# board.net
KiCad netlist of a schematic drawn in EAGLE
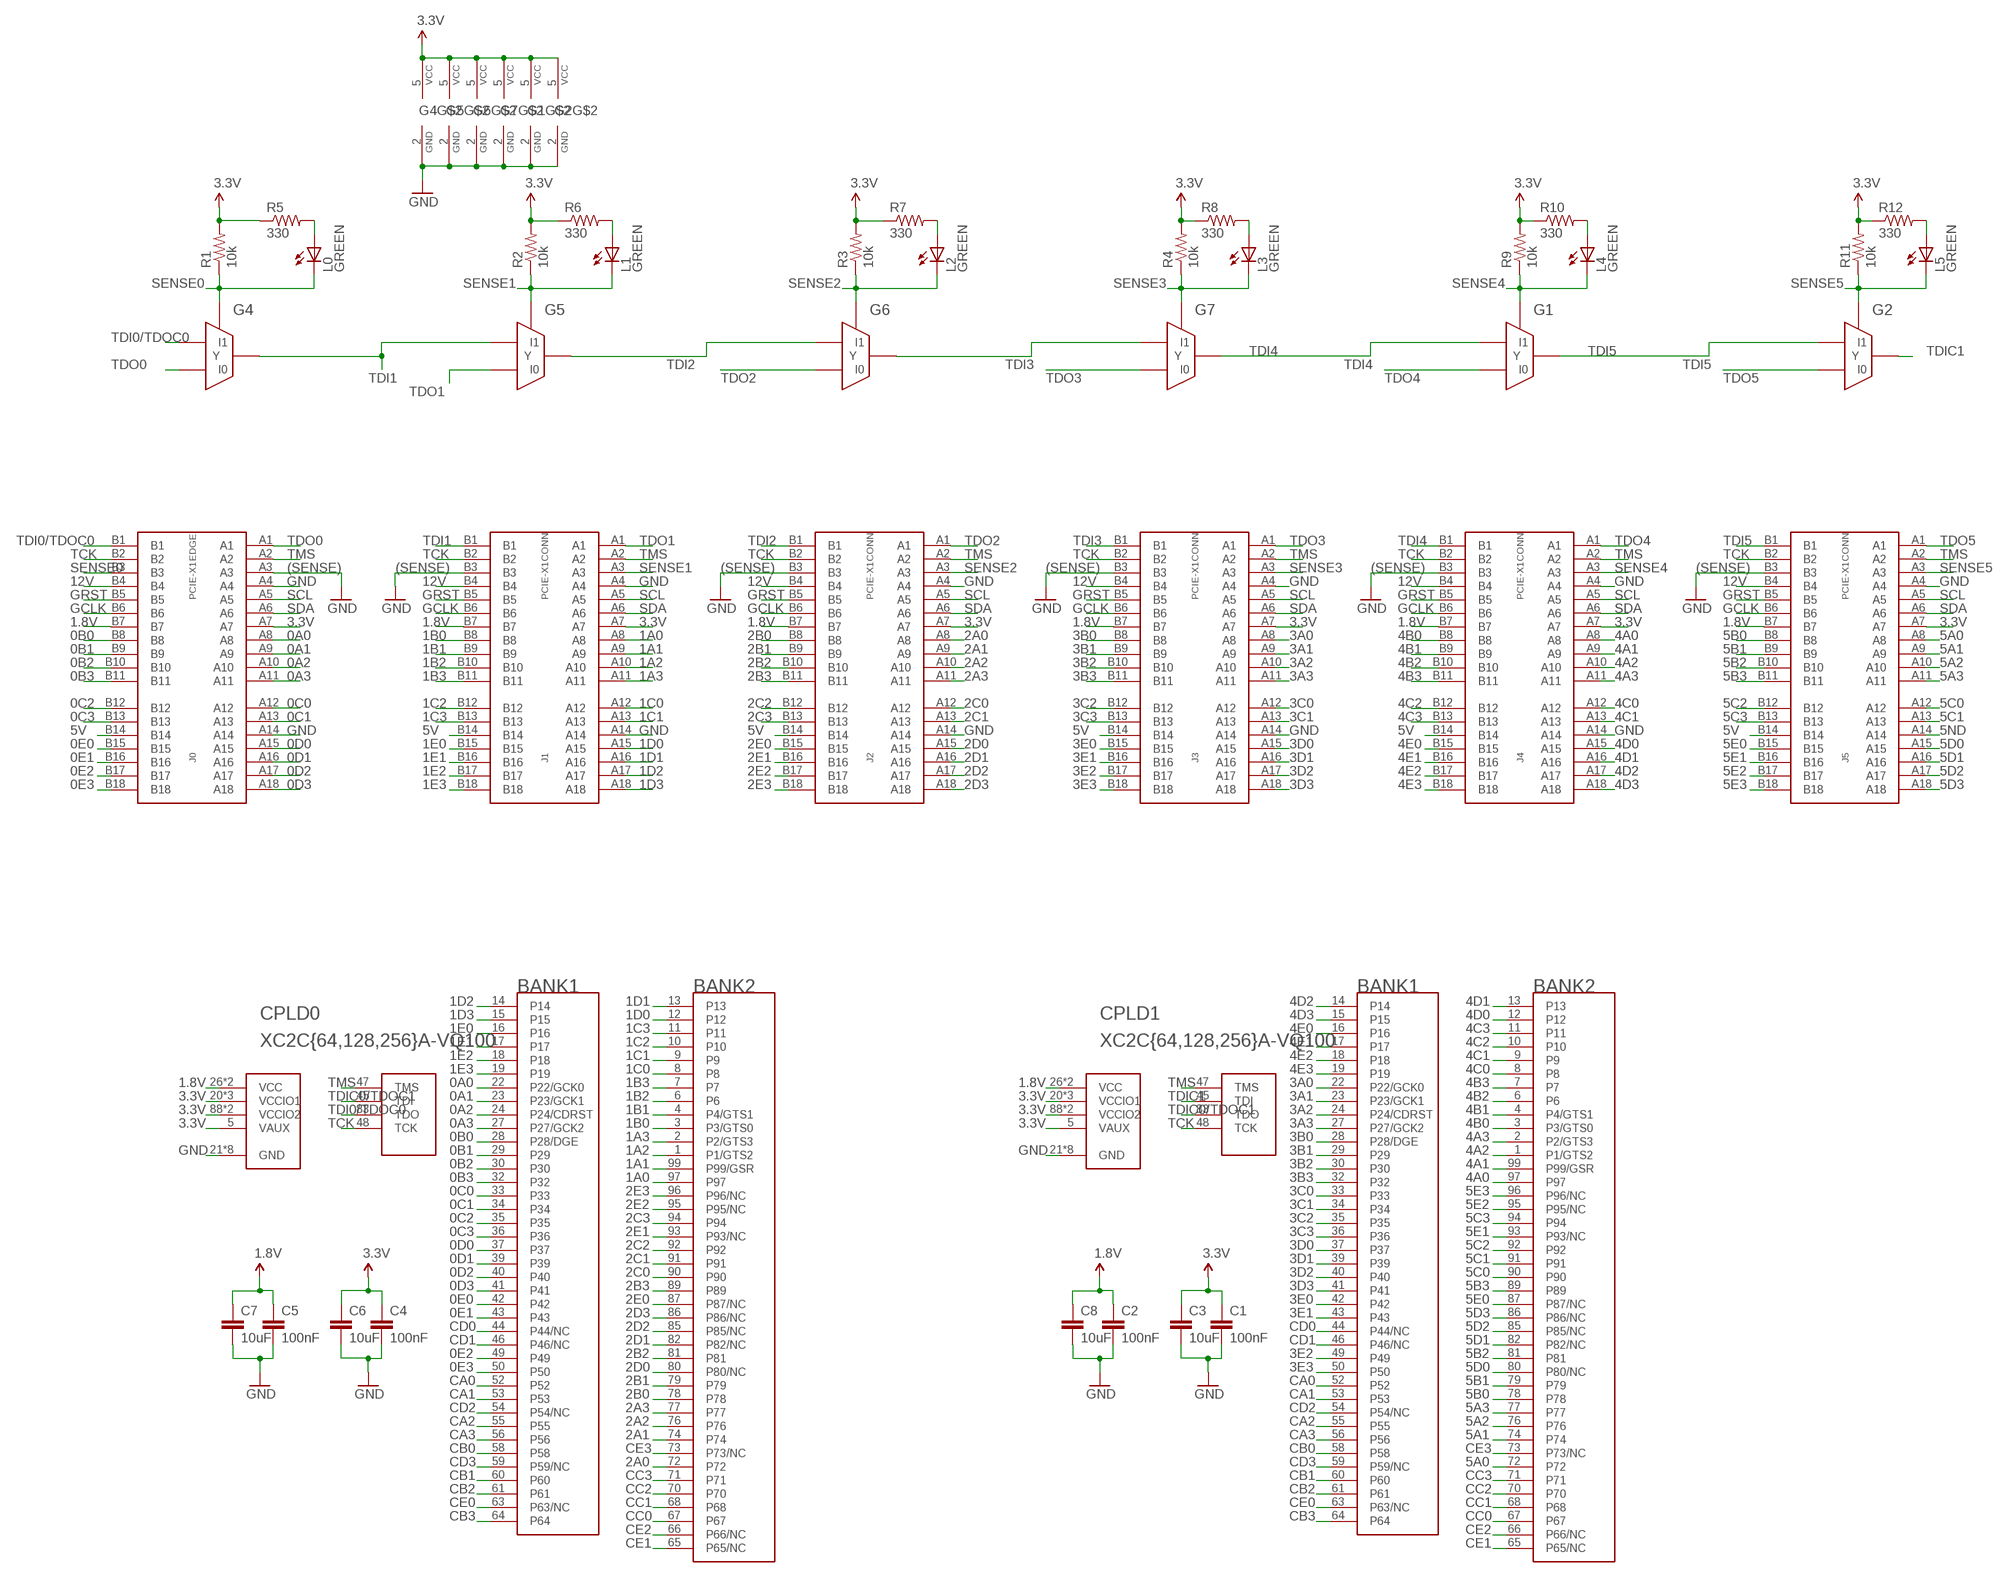
[diagram p0: schematic, sheet 1]

(export (version "E")
  (design (tool "Eeschema 10.0.6"))
  (components
    (comp (ref "C1")
      (value "100nF")
      (footprint "eagle-import:0402-CAP")
      (libsource (lib "eagle-import") (part "CAP0402-CAP"))
    )
    (comp (ref "C2")
      (value "100nF")
      (footprint "eagle-import:0402-CAP")
      (libsource (lib "eagle-import") (part "CAP0402-CAP"))
    )
    (comp (ref "C3")
      (value "10uF")
      (footprint "eagle-import:0805")
      (libsource (lib "eagle-import") (part "CAP0805"))
    )
    (comp (ref "C4")
      (value "100nF")
      (footprint "eagle-import:0402-CAP")
      (libsource (lib "eagle-import") (part "CAP0402-CAP"))
    )
    (comp (ref "C5")
      (value "100nF")
      (footprint "eagle-import:0402-CAP")
      (libsource (lib "eagle-import") (part "CAP0402-CAP"))
    )
    (comp (ref "C6")
      (value "10uF")
      (footprint "eagle-import:0805")
      (libsource (lib "eagle-import") (part "CAP0805"))
    )
    (comp (ref "C7")
      (value "10uF")
      (footprint "eagle-import:0805")
      (libsource (lib "eagle-import") (part "CAP0805"))
    )
    (comp (ref "C8")
      (value "10uF")
      (footprint "eagle-import:0805")
      (libsource (lib "eagle-import") (part "CAP0805"))
    )
    (comp (ref "CPLD0")
      (value "XC2C{64,128,256}A-VQ100")
      (footprint "eagle-import:XILINX_TQ100")
      (libsource (lib "eagle-import") (part "XC2C{64,128,256}A-VQ100"))
    )
    (comp (ref "CPLD1")
      (value "XC2C{64,128,256}A-VQ100")
      (footprint "eagle-import:XILINX_TQ100")
      (libsource (lib "eagle-import") (part "XC2C{64,128,256}A-VQ100"))
    )
    (comp (ref "G1")
      (value "74G157")
      (footprint "eagle-import:SOT363")
      (libsource (lib "eagle-import") (part "74G157"))
    )
    (comp (ref "G2")
      (value "74G157")
      (footprint "eagle-import:SOT363")
      (libsource (lib "eagle-import") (part "74G157"))
    )
    (comp (ref "G4")
      (value "74G157")
      (footprint "eagle-import:SOT363")
      (libsource (lib "eagle-import") (part "74G157"))
    )
    (comp (ref "G5")
      (value "74G157")
      (footprint "eagle-import:SOT363")
      (libsource (lib "eagle-import") (part "74G157"))
    )
    (comp (ref "G6")
      (value "74G157")
      (footprint "eagle-import:SOT363")
      (libsource (lib "eagle-import") (part "74G157"))
    )
    (comp (ref "G7")
      (value "74G157")
      (footprint "eagle-import:SOT363")
      (libsource (lib "eagle-import") (part "74G157"))
    )
    (comp (ref "J0")
      (value "PCIE-X1EDGE")
      (footprint "eagle-import:PCIE-X1-EDGE")
      (libsource (lib "eagle-import") (part "PCIE-X1EDGE"))
    )
    (comp (ref "J1")
      (value "PCIE-X1CONN")
      (footprint "eagle-import:PCIE-X1-CONN")
      (libsource (lib "eagle-import") (part "PCIE-X1CONN"))
    )
    (comp (ref "J2")
      (value "PCIE-X1CONN")
      (footprint "eagle-import:PCIE-X1-CONN")
      (libsource (lib "eagle-import") (part "PCIE-X1CONN"))
    )
    (comp (ref "J3")
      (value "PCIE-X1CONN")
      (footprint "eagle-import:PCIE-X1-CONN")
      (libsource (lib "eagle-import") (part "PCIE-X1CONN"))
    )
    (comp (ref "J4")
      (value "PCIE-X1CONN")
      (footprint "eagle-import:PCIE-X1-CONN")
      (libsource (lib "eagle-import") (part "PCIE-X1CONN"))
    )
    (comp (ref "J5")
      (value "PCIE-X1CONN")
      (footprint "eagle-import:PCIE-X1-CONN")
      (libsource (lib "eagle-import") (part "PCIE-X1CONN"))
    )
    (comp (ref "L0")
      (value "GREEN")
      (footprint "eagle-import:0603_LED")
      (libsource (lib "eagle-import") (part "LED0603"))
    )
    (comp (ref "L1")
      (value "GREEN")
      (footprint "eagle-import:0603_LED")
      (libsource (lib "eagle-import") (part "LED0603"))
    )
    (comp (ref "L2")
      (value "GREEN")
      (footprint "eagle-import:0603_LED")
      (libsource (lib "eagle-import") (part "LED0603"))
    )
    (comp (ref "L3")
      (value "GREEN")
      (footprint "eagle-import:0603_LED")
      (libsource (lib "eagle-import") (part "LED0603"))
    )
    (comp (ref "L4")
      (value "GREEN")
      (footprint "eagle-import:0603_LED")
      (libsource (lib "eagle-import") (part "LED0603"))
    )
    (comp (ref "L5")
      (value "GREEN")
      (footprint "eagle-import:0603_LED")
      (libsource (lib "eagle-import") (part "LED0603"))
    )
    (comp (ref "R1")
      (value "10k")
      (footprint "eagle-import:0603-RES")
      (libsource (lib "eagle-import") (part "RESISTOR0603"))
    )
    (comp (ref "R2")
      (value "10k")
      (footprint "eagle-import:0603-RES")
      (libsource (lib "eagle-import") (part "RESISTOR0603"))
    )
    (comp (ref "R3")
      (value "10k")
      (footprint "eagle-import:0603-RES")
      (libsource (lib "eagle-import") (part "RESISTOR0603"))
    )
    (comp (ref "R4")
      (value "10k")
      (footprint "eagle-import:0603-RES")
      (libsource (lib "eagle-import") (part "RESISTOR0603"))
    )
    (comp (ref "R5")
      (value "330")
      (footprint "eagle-import:0603-RES")
      (libsource (lib "eagle-import") (part "RESISTOR0603"))
    )
    (comp (ref "R6")
      (value "330")
      (footprint "eagle-import:0603-RES")
      (libsource (lib "eagle-import") (part "RESISTOR0603"))
    )
    (comp (ref "R7")
      (value "330")
      (footprint "eagle-import:0603-RES")
      (libsource (lib "eagle-import") (part "RESISTOR0603"))
    )
    (comp (ref "R8")
      (value "330")
      (footprint "eagle-import:0603-RES")
      (libsource (lib "eagle-import") (part "RESISTOR0603"))
    )
    (comp (ref "R9")
      (value "10k")
      (footprint "eagle-import:0603-RES")
      (libsource (lib "eagle-import") (part "RESISTOR0603"))
    )
    (comp (ref "R10")
      (value "330")
      (footprint "eagle-import:0603-RES")
      (libsource (lib "eagle-import") (part "RESISTOR0603"))
    )
    (comp (ref "R11")
      (value "10k")
      (footprint "eagle-import:0603-RES")
      (libsource (lib "eagle-import") (part "RESISTOR0603"))
    )
    (comp (ref "R12")
      (value "330")
      (footprint "eagle-import:0603-RES")
      (libsource (lib "eagle-import") (part "RESISTOR0603"))
    )
  )
  (nets
    (net (code "1") (name "/0A0") (class "Default")
      (node (ref "CPLD0") (pin "22") (pinfunction "P22/GCK0_22") (pintype "bidirectional"))
      (node (ref "J0") (pin "A8") (pinfunction "A8_A8") (pintype "bidirectional"))
    )
    (net (code "2") (name "/0A1") (class "Default")
      (node (ref "CPLD0") (pin "23") (pinfunction "P23/GCK1_23") (pintype "bidirectional"))
      (node (ref "J0") (pin "A9") (pinfunction "A9_A9") (pintype "bidirectional"))
    )
    (net (code "3") (name "/0A2") (class "Default")
      (node (ref "CPLD0") (pin "24") (pinfunction "P24/CDRST_24") (pintype "bidirectional"))
      (node (ref "J0") (pin "A10") (pinfunction "A10_A10") (pintype "bidirectional"))
    )
    (net (code "4") (name "/0A3") (class "Default")
      (node (ref "CPLD0") (pin "27") (pinfunction "P27/GCK2_27") (pintype "bidirectional"))
      (node (ref "J0") (pin "A11") (pinfunction "A11_A11") (pintype "bidirectional"))
    )
    (net (code "5") (name "/0B0") (class "Default")
      (node (ref "CPLD0") (pin "28") (pinfunction "P28/DGE_28") (pintype "bidirectional"))
      (node (ref "J0") (pin "B8") (pinfunction "B8_B8") (pintype "bidirectional"))
    )
    (net (code "6") (name "/0B1") (class "Default")
      (node (ref "CPLD0") (pin "29") (pinfunction "P29_29") (pintype "bidirectional"))
      (node (ref "J0") (pin "B9") (pinfunction "B9_B9") (pintype "bidirectional"))
    )
    (net (code "7") (name "/0B2") (class "Default")
      (node (ref "CPLD0") (pin "30") (pinfunction "P30_30") (pintype "bidirectional"))
      (node (ref "J0") (pin "B10") (pinfunction "B10_B10") (pintype "bidirectional"))
    )
    (net (code "8") (name "/0B3") (class "Default")
      (node (ref "CPLD0") (pin "32") (pinfunction "P32_32") (pintype "bidirectional"))
      (node (ref "J0") (pin "B11") (pinfunction "B11_B11") (pintype "bidirectional"))
    )
    (net (code "9") (name "/0C0") (class "Default")
      (node (ref "CPLD0") (pin "33") (pinfunction "P33_33") (pintype "bidirectional"))
      (node (ref "J0") (pin "A12") (pinfunction "A12_A12") (pintype "bidirectional"))
    )
    (net (code "10") (name "/0C1") (class "Default")
      (node (ref "CPLD0") (pin "34") (pinfunction "P34_34") (pintype "bidirectional"))
      (node (ref "J0") (pin "A13") (pinfunction "A13_A13") (pintype "bidirectional"))
    )
    (net (code "11") (name "/0C2") (class "Default")
      (node (ref "CPLD0") (pin "35") (pinfunction "P35_35") (pintype "bidirectional"))
      (node (ref "J0") (pin "B12") (pinfunction "B12_B12") (pintype "bidirectional"))
    )
    (net (code "12") (name "/0C3") (class "Default")
      (node (ref "CPLD0") (pin "36") (pinfunction "P36_36") (pintype "bidirectional"))
      (node (ref "J0") (pin "B13") (pinfunction "B13_B13") (pintype "bidirectional"))
    )
    (net (code "13") (name "/0D0") (class "Default")
      (node (ref "CPLD0") (pin "37") (pinfunction "P37_37") (pintype "bidirectional"))
      (node (ref "J0") (pin "A15") (pinfunction "A15_A15") (pintype "bidirectional"))
    )
    (net (code "14") (name "/0D1") (class "Default")
      (node (ref "CPLD0") (pin "39") (pinfunction "P39_39") (pintype "bidirectional"))
      (node (ref "J0") (pin "A16") (pinfunction "A16_A16") (pintype "bidirectional"))
    )
    (net (code "15") (name "/0D2") (class "Default")
      (node (ref "CPLD0") (pin "40") (pinfunction "P40_40") (pintype "bidirectional"))
      (node (ref "J0") (pin "A17") (pinfunction "A17_A17") (pintype "bidirectional"))
    )
    (net (code "16") (name "/0D3") (class "Default")
      (node (ref "CPLD0") (pin "41") (pinfunction "P41_41") (pintype "bidirectional"))
      (node (ref "J0") (pin "A18") (pinfunction "A18_A18") (pintype "bidirectional"))
    )
    (net (code "17") (name "/0E0") (class "Default")
      (node (ref "CPLD0") (pin "42") (pinfunction "P42_42") (pintype "bidirectional"))
      (node (ref "J0") (pin "B15") (pinfunction "B15_B15") (pintype "bidirectional"))
    )
    (net (code "18") (name "/0E1") (class "Default")
      (node (ref "CPLD0") (pin "43") (pinfunction "P43_43") (pintype "bidirectional"))
      (node (ref "J0") (pin "B16") (pinfunction "B16_B16") (pintype "bidirectional"))
    )
    (net (code "19") (name "/0E2") (class "Default")
      (node (ref "CPLD0") (pin "49") (pinfunction "P49_49") (pintype "bidirectional"))
      (node (ref "J0") (pin "B17") (pinfunction "B17_B17") (pintype "bidirectional"))
    )
    (net (code "20") (name "/0E3") (class "Default")
      (node (ref "CPLD0") (pin "50") (pinfunction "P50_50") (pintype "bidirectional"))
      (node (ref "J0") (pin "B18") (pinfunction "B18_B18") (pintype "bidirectional"))
    )
    (net (code "21") (name "/1A0") (class "Default")
      (node (ref "CPLD0") (pin "97") (pinfunction "P97_97") (pintype "bidirectional"))
      (node (ref "J1") (pin "A8") (pinfunction "A8_A8") (pintype "bidirectional"))
    )
    (net (code "22") (name "/1A1") (class "Default")
      (node (ref "CPLD0") (pin "99") (pinfunction "P99/GSR_99") (pintype "bidirectional"))
      (node (ref "J1") (pin "A9") (pinfunction "A9_A9") (pintype "bidirectional"))
    )
    (net (code "23") (name "/1A2") (class "Default")
      (node (ref "CPLD0") (pin "1") (pinfunction "P1/GTS2_1") (pintype "bidirectional"))
      (node (ref "J1") (pin "A10") (pinfunction "A10_A10") (pintype "bidirectional"))
    )
    (net (code "24") (name "/1A3") (class "Default")
      (node (ref "CPLD0") (pin "2") (pinfunction "P2/GTS3_2") (pintype "bidirectional"))
      (node (ref "J1") (pin "A11") (pinfunction "A11_A11") (pintype "bidirectional"))
    )
    (net (code "25") (name "/1B0") (class "Default")
      (node (ref "CPLD0") (pin "3") (pinfunction "P3/GTS0_3") (pintype "bidirectional"))
      (node (ref "J1") (pin "B8") (pinfunction "B8_B8") (pintype "bidirectional"))
    )
    (net (code "26") (name "/1B1") (class "Default")
      (node (ref "CPLD0") (pin "4") (pinfunction "P4/GTS1_4") (pintype "bidirectional"))
      (node (ref "J1") (pin "B9") (pinfunction "B9_B9") (pintype "bidirectional"))
    )
    (net (code "27") (name "/1B2") (class "Default")
      (node (ref "CPLD0") (pin "6") (pinfunction "P6_6") (pintype "bidirectional"))
      (node (ref "J1") (pin "B10") (pinfunction "B10_B10") (pintype "bidirectional"))
    )
    (net (code "28") (name "/1B3") (class "Default")
      (node (ref "CPLD0") (pin "7") (pinfunction "P7_7") (pintype "bidirectional"))
      (node (ref "J1") (pin "B11") (pinfunction "B11_B11") (pintype "bidirectional"))
    )
    (net (code "29") (name "/1C0") (class "Default")
      (node (ref "CPLD0") (pin "8") (pinfunction "P8_8") (pintype "bidirectional"))
      (node (ref "J1") (pin "A12") (pinfunction "A12_A12") (pintype "bidirectional"))
    )
    (net (code "30") (name "/1C1") (class "Default")
      (node (ref "CPLD0") (pin "9") (pinfunction "P9_9") (pintype "bidirectional"))
      (node (ref "J1") (pin "A13") (pinfunction "A13_A13") (pintype "bidirectional"))
    )
    (net (code "31") (name "/1C2") (class "Default")
      (node (ref "CPLD0") (pin "10") (pinfunction "P10_10") (pintype "bidirectional"))
      (node (ref "J1") (pin "B12") (pinfunction "B12_B12") (pintype "bidirectional"))
    )
    (net (code "32") (name "/1C3") (class "Default")
      (node (ref "CPLD0") (pin "11") (pinfunction "P11_11") (pintype "bidirectional"))
      (node (ref "J1") (pin "B13") (pinfunction "B13_B13") (pintype "bidirectional"))
    )
    (net (code "33") (name "/1D0") (class "Default")
      (node (ref "CPLD0") (pin "12") (pinfunction "P12_12") (pintype "bidirectional"))
      (node (ref "J1") (pin "A15") (pinfunction "A15_A15") (pintype "bidirectional"))
    )
    (net (code "34") (name "/1D1") (class "Default")
      (node (ref "CPLD0") (pin "13") (pinfunction "P13_13") (pintype "bidirectional"))
      (node (ref "J1") (pin "A16") (pinfunction "A16_A16") (pintype "bidirectional"))
    )
    (net (code "35") (name "/1D2") (class "Default")
      (node (ref "CPLD0") (pin "14") (pinfunction "P14_14") (pintype "bidirectional"))
      (node (ref "J1") (pin "A17") (pinfunction "A17_A17") (pintype "bidirectional"))
    )
    (net (code "36") (name "/1D3") (class "Default")
      (node (ref "CPLD0") (pin "15") (pinfunction "P15_15") (pintype "bidirectional"))
      (node (ref "J1") (pin "A18") (pinfunction "A18_A18") (pintype "bidirectional"))
    )
    (net (code "37") (name "/1E0") (class "Default")
      (node (ref "CPLD0") (pin "16") (pinfunction "P16_16") (pintype "bidirectional"))
      (node (ref "J1") (pin "B15") (pinfunction "B15_B15") (pintype "bidirectional"))
    )
    (net (code "38") (name "/1E1") (class "Default")
      (node (ref "CPLD0") (pin "17") (pinfunction "P17_17") (pintype "bidirectional"))
      (node (ref "J1") (pin "B16") (pinfunction "B16_B16") (pintype "bidirectional"))
    )
    (net (code "39") (name "/1E2") (class "Default")
      (node (ref "CPLD0") (pin "18") (pinfunction "P18_18") (pintype "bidirectional"))
      (node (ref "J1") (pin "B17") (pinfunction "B17_B17") (pintype "bidirectional"))
    )
    (net (code "40") (name "/1E3") (class "Default")
      (node (ref "CPLD0") (pin "19") (pinfunction "P19_19") (pintype "bidirectional"))
      (node (ref "J1") (pin "B18") (pinfunction "B18_B18") (pintype "bidirectional"))
    )
    (net (code "41") (name "/2A0") (class "Default")
      (node (ref "CPLD0") (pin "72") (pinfunction "P72_72") (pintype "bidirectional"))
      (node (ref "J2") (pin "A8") (pinfunction "A8_A8") (pintype "bidirectional"))
    )
    (net (code "42") (name "/2A1") (class "Default")
      (node (ref "CPLD0") (pin "74") (pinfunction "P74_74") (pintype "bidirectional"))
      (node (ref "J2") (pin "A9") (pinfunction "A9_A9") (pintype "bidirectional"))
    )
    (net (code "43") (name "/2A2") (class "Default")
      (node (ref "CPLD0") (pin "76") (pinfunction "P76_76") (pintype "bidirectional"))
      (node (ref "J2") (pin "A10") (pinfunction "A10_A10") (pintype "bidirectional"))
    )
    (net (code "44") (name "/2A3") (class "Default")
      (node (ref "CPLD0") (pin "77") (pinfunction "P77_77") (pintype "bidirectional"))
      (node (ref "J2") (pin "A11") (pinfunction "A11_A11") (pintype "bidirectional"))
    )
    (net (code "45") (name "/2B0") (class "Default")
      (node (ref "CPLD0") (pin "78") (pinfunction "P78_78") (pintype "bidirectional"))
      (node (ref "J2") (pin "B8") (pinfunction "B8_B8") (pintype "bidirectional"))
    )
    (net (code "46") (name "/2B1") (class "Default")
      (node (ref "CPLD0") (pin "79") (pinfunction "P79_79") (pintype "bidirectional"))
      (node (ref "J2") (pin "B9") (pinfunction "B9_B9") (pintype "bidirectional"))
    )
    (net (code "47") (name "/2B2") (class "Default")
      (node (ref "CPLD0") (pin "81") (pinfunction "P81_81") (pintype "bidirectional"))
      (node (ref "J2") (pin "B10") (pinfunction "B10_B10") (pintype "bidirectional"))
    )
    (net (code "48") (name "/2B3") (class "Default")
      (node (ref "CPLD0") (pin "89") (pinfunction "P89_89") (pintype "bidirectional"))
      (node (ref "J2") (pin "B11") (pinfunction "B11_B11") (pintype "bidirectional"))
    )
    (net (code "49") (name "/2C0") (class "Default")
      (node (ref "CPLD0") (pin "90") (pinfunction "P90_90") (pintype "bidirectional"))
      (node (ref "J2") (pin "A12") (pinfunction "A12_A12") (pintype "bidirectional"))
    )
    (net (code "50") (name "/2C1") (class "Default")
      (node (ref "CPLD0") (pin "91") (pinfunction "P91_91") (pintype "bidirectional"))
      (node (ref "J2") (pin "A13") (pinfunction "A13_A13") (pintype "bidirectional"))
    )
    (net (code "51") (name "/2C2") (class "Default")
      (node (ref "CPLD0") (pin "92") (pinfunction "P92_92") (pintype "bidirectional"))
      (node (ref "J2") (pin "B12") (pinfunction "B12_B12") (pintype "bidirectional"))
    )
    (net (code "52") (name "/2C3") (class "Default")
      (node (ref "CPLD0") (pin "94") (pinfunction "P94_94") (pintype "bidirectional"))
      (node (ref "J2") (pin "B13") (pinfunction "B13_B13") (pintype "bidirectional"))
    )
    (net (code "53") (name "/2D0") (class "Default")
      (node (ref "CPLD0") (pin "80") (pinfunction "P80/NC_80") (pintype "bidirectional"))
      (node (ref "J2") (pin "A15") (pinfunction "A15_A15") (pintype "bidirectional"))
    )
    (net (code "54") (name "/2D1") (class "Default")
      (node (ref "CPLD0") (pin "82") (pinfunction "P82/NC_82") (pintype "bidirectional"))
      (node (ref "J2") (pin "A16") (pinfunction "A16_A16") (pintype "bidirectional"))
    )
    (net (code "55") (name "/2D2") (class "Default")
      (node (ref "CPLD0") (pin "85") (pinfunction "P85/NC_85") (pintype "bidirectional"))
      (node (ref "J2") (pin "A17") (pinfunction "A17_A17") (pintype "bidirectional"))
    )
    (net (code "56") (name "/2D3") (class "Default")
      (node (ref "CPLD0") (pin "86") (pinfunction "P86/NC_86") (pintype "bidirectional"))
      (node (ref "J2") (pin "A18") (pinfunction "A18_A18") (pintype "bidirectional"))
    )
    (net (code "57") (name "/2E0") (class "Default")
      (node (ref "CPLD0") (pin "87") (pinfunction "P87/NC_87") (pintype "bidirectional"))
      (node (ref "J2") (pin "B15") (pinfunction "B15_B15") (pintype "bidirectional"))
    )
    (net (code "58") (name "/2E1") (class "Default")
      (node (ref "CPLD0") (pin "93") (pinfunction "P93/NC_93") (pintype "bidirectional"))
      (node (ref "J2") (pin "B16") (pinfunction "B16_B16") (pintype "bidirectional"))
    )
    (net (code "59") (name "/2E2") (class "Default")
      (node (ref "CPLD0") (pin "95") (pinfunction "P95/NC_95") (pintype "bidirectional"))
      (node (ref "J2") (pin "B17") (pinfunction "B17_B17") (pintype "bidirectional"))
    )
    (net (code "60") (name "/2E3") (class "Default")
      (node (ref "CPLD0") (pin "96") (pinfunction "P96/NC_96") (pintype "bidirectional"))
      (node (ref "J2") (pin "B18") (pinfunction "B18_B18") (pintype "bidirectional"))
    )
    (net (code "61") (name "/3A0") (class "Default")
      (node (ref "CPLD1") (pin "22") (pinfunction "P22/GCK0_22") (pintype "bidirectional"))
      (node (ref "J3") (pin "A8") (pinfunction "A8_A8") (pintype "bidirectional"))
    )
    (net (code "62") (name "/3A1") (class "Default")
      (node (ref "CPLD1") (pin "23") (pinfunction "P23/GCK1_23") (pintype "bidirectional"))
      (node (ref "J3") (pin "A9") (pinfunction "A9_A9") (pintype "bidirectional"))
    )
    (net (code "63") (name "/3A2") (class "Default")
      (node (ref "CPLD1") (pin "24") (pinfunction "P24/CDRST_24") (pintype "bidirectional"))
      (node (ref "J3") (pin "A10") (pinfunction "A10_A10") (pintype "bidirectional"))
    )
    (net (code "64") (name "/3A3") (class "Default")
      (node (ref "CPLD1") (pin "27") (pinfunction "P27/GCK2_27") (pintype "bidirectional"))
      (node (ref "J3") (pin "A11") (pinfunction "A11_A11") (pintype "bidirectional"))
    )
    (net (code "65") (name "/3B0") (class "Default")
      (node (ref "CPLD1") (pin "28") (pinfunction "P28/DGE_28") (pintype "bidirectional"))
      (node (ref "J3") (pin "B8") (pinfunction "B8_B8") (pintype "bidirectional"))
    )
    (net (code "66") (name "/3B1") (class "Default")
      (node (ref "CPLD1") (pin "29") (pinfunction "P29_29") (pintype "bidirectional"))
      (node (ref "J3") (pin "B9") (pinfunction "B9_B9") (pintype "bidirectional"))
    )
    (net (code "67") (name "/3B2") (class "Default")
      (node (ref "CPLD1") (pin "30") (pinfunction "P30_30") (pintype "bidirectional"))
      (node (ref "J3") (pin "B10") (pinfunction "B10_B10") (pintype "bidirectional"))
    )
    (net (code "68") (name "/3B3") (class "Default")
      (node (ref "CPLD1") (pin "32") (pinfunction "P32_32") (pintype "bidirectional"))
      (node (ref "J3") (pin "B11") (pinfunction "B11_B11") (pintype "bidirectional"))
    )
    (net (code "69") (name "/3C0") (class "Default")
      (node (ref "CPLD1") (pin "33") (pinfunction "P33_33") (pintype "bidirectional"))
      (node (ref "J3") (pin "A12") (pinfunction "A12_A12") (pintype "bidirectional"))
    )
    (net (code "70") (name "/3C1") (class "Default")
      (node (ref "CPLD1") (pin "34") (pinfunction "P34_34") (pintype "bidirectional"))
      (node (ref "J3") (pin "A13") (pinfunction "A13_A13") (pintype "bidirectional"))
    )
    (net (code "71") (name "/3C2") (class "Default")
      (node (ref "CPLD1") (pin "35") (pinfunction "P35_35") (pintype "bidirectional"))
      (node (ref "J3") (pin "B12") (pinfunction "B12_B12") (pintype "bidirectional"))
    )
    (net (code "72") (name "/3C3") (class "Default")
      (node (ref "CPLD1") (pin "36") (pinfunction "P36_36") (pintype "bidirectional"))
      (node (ref "J3") (pin "B13") (pinfunction "B13_B13") (pintype "bidirectional"))
    )
    (net (code "73") (name "/3D0") (class "Default")
      (node (ref "CPLD1") (pin "37") (pinfunction "P37_37") (pintype "bidirectional"))
      (node (ref "J3") (pin "A15") (pinfunction "A15_A15") (pintype "bidirectional"))
    )
    (net (code "74") (name "/3D1") (class "Default")
      (node (ref "CPLD1") (pin "39") (pinfunction "P39_39") (pintype "bidirectional"))
      (node (ref "J3") (pin "A16") (pinfunction "A16_A16") (pintype "bidirectional"))
    )
    (net (code "75") (name "/3D2") (class "Default")
      (node (ref "CPLD1") (pin "40") (pinfunction "P40_40") (pintype "bidirectional"))
      (node (ref "J3") (pin "A17") (pinfunction "A17_A17") (pintype "bidirectional"))
    )
    (net (code "76") (name "/3D3") (class "Default")
      (node (ref "CPLD1") (pin "41") (pinfunction "P41_41") (pintype "bidirectional"))
      (node (ref "J3") (pin "A18") (pinfunction "A18_A18") (pintype "bidirectional"))
    )
    (net (code "77") (name "/3E0") (class "Default")
      (node (ref "CPLD1") (pin "42") (pinfunction "P42_42") (pintype "bidirectional"))
      (node (ref "J3") (pin "B15") (pinfunction "B15_B15") (pintype "bidirectional"))
    )
    (net (code "78") (name "/3E1") (class "Default")
      (node (ref "CPLD1") (pin "43") (pinfunction "P43_43") (pintype "bidirectional"))
      (node (ref "J3") (pin "B16") (pinfunction "B16_B16") (pintype "bidirectional"))
    )
    (net (code "79") (name "/3E2") (class "Default")
      (node (ref "CPLD1") (pin "49") (pinfunction "P49_49") (pintype "bidirectional"))
      (node (ref "J3") (pin "B17") (pinfunction "B17_B17") (pintype "bidirectional"))
    )
    (net (code "80") (name "/3E3") (class "Default")
      (node (ref "CPLD1") (pin "50") (pinfunction "P50_50") (pintype "bidirectional"))
      (node (ref "J3") (pin "B18") (pinfunction "B18_B18") (pintype "bidirectional"))
    )
    (net (code "81") (name "/4A0") (class "Default")
      (node (ref "CPLD1") (pin "97") (pinfunction "P97_97") (pintype "bidirectional"))
      (node (ref "J4") (pin "A8") (pinfunction "A8_A8") (pintype "bidirectional"))
    )
    (net (code "82") (name "/4A1") (class "Default")
      (node (ref "CPLD1") (pin "99") (pinfunction "P99/GSR_99") (pintype "bidirectional"))
      (node (ref "J4") (pin "A9") (pinfunction "A9_A9") (pintype "bidirectional"))
    )
    (net (code "83") (name "/4A2") (class "Default")
      (node (ref "CPLD1") (pin "1") (pinfunction "P1/GTS2_1") (pintype "bidirectional"))
      (node (ref "J4") (pin "A10") (pinfunction "A10_A10") (pintype "bidirectional"))
    )
    (net (code "84") (name "/4A3") (class "Default")
      (node (ref "CPLD1") (pin "2") (pinfunction "P2/GTS3_2") (pintype "bidirectional"))
      (node (ref "J4") (pin "A11") (pinfunction "A11_A11") (pintype "bidirectional"))
    )
    (net (code "85") (name "/4B0") (class "Default")
      (node (ref "CPLD1") (pin "3") (pinfunction "P3/GTS0_3") (pintype "bidirectional"))
      (node (ref "J4") (pin "B8") (pinfunction "B8_B8") (pintype "bidirectional"))
    )
    (net (code "86") (name "/4B1") (class "Default")
      (node (ref "CPLD1") (pin "4") (pinfunction "P4/GTS1_4") (pintype "bidirectional"))
      (node (ref "J4") (pin "B9") (pinfunction "B9_B9") (pintype "bidirectional"))
    )
    (net (code "87") (name "/4B2") (class "Default")
      (node (ref "CPLD1") (pin "6") (pinfunction "P6_6") (pintype "bidirectional"))
      (node (ref "J4") (pin "B10") (pinfunction "B10_B10") (pintype "bidirectional"))
    )
    (net (code "88") (name "/4B3") (class "Default")
      (node (ref "CPLD1") (pin "7") (pinfunction "P7_7") (pintype "bidirectional"))
      (node (ref "J4") (pin "B11") (pinfunction "B11_B11") (pintype "bidirectional"))
    )
    (net (code "89") (name "/4C0") (class "Default")
      (node (ref "CPLD1") (pin "8") (pinfunction "P8_8") (pintype "bidirectional"))
      (node (ref "J4") (pin "A12") (pinfunction "A12_A12") (pintype "bidirectional"))
    )
    (net (code "90") (name "/4C1") (class "Default")
      (node (ref "CPLD1") (pin "9") (pinfunction "P9_9") (pintype "bidirectional"))
      (node (ref "J4") (pin "A13") (pinfunction "A13_A13") (pintype "bidirectional"))
    )
    (net (code "91") (name "/4C2") (class "Default")
      (node (ref "CPLD1") (pin "10") (pinfunction "P10_10") (pintype "bidirectional"))
      (node (ref "J4") (pin "B12") (pinfunction "B12_B12") (pintype "bidirectional"))
    )
    (net (code "92") (name "/4C3") (class "Default")
      (node (ref "CPLD1") (pin "11") (pinfunction "P11_11") (pintype "bidirectional"))
      (node (ref "J4") (pin "B13") (pinfunction "B13_B13") (pintype "bidirectional"))
    )
    (net (code "93") (name "/4D0") (class "Default")
      (node (ref "CPLD1") (pin "12") (pinfunction "P12_12") (pintype "bidirectional"))
      (node (ref "J4") (pin "A15") (pinfunction "A15_A15") (pintype "bidirectional"))
    )
    (net (code "94") (name "/4D1") (class "Default")
      (node (ref "CPLD1") (pin "13") (pinfunction "P13_13") (pintype "bidirectional"))
      (node (ref "J4") (pin "A16") (pinfunction "A16_A16") (pintype "bidirectional"))
    )
    (net (code "95") (name "/4D2") (class "Default")
      (node (ref "CPLD1") (pin "14") (pinfunction "P14_14") (pintype "bidirectional"))
      (node (ref "J4") (pin "A17") (pinfunction "A17_A17") (pintype "bidirectional"))
    )
    (net (code "96") (name "/4D3") (class "Default")
      (node (ref "CPLD1") (pin "15") (pinfunction "P15_15") (pintype "bidirectional"))
      (node (ref "J4") (pin "A18") (pinfunction "A18_A18") (pintype "bidirectional"))
    )
    (net (code "97") (name "/4E0") (class "Default")
      (node (ref "CPLD1") (pin "16") (pinfunction "P16_16") (pintype "bidirectional"))
      (node (ref "J4") (pin "B15") (pinfunction "B15_B15") (pintype "bidirectional"))
    )
    (net (code "98") (name "/4E1") (class "Default")
      (node (ref "CPLD1") (pin "17") (pinfunction "P17_17") (pintype "bidirectional"))
      (node (ref "J4") (pin "B16") (pinfunction "B16_B16") (pintype "bidirectional"))
    )
    (net (code "99") (name "/4E2") (class "Default")
      (node (ref "CPLD1") (pin "18") (pinfunction "P18_18") (pintype "bidirectional"))
      (node (ref "J4") (pin "B17") (pinfunction "B17_B17") (pintype "bidirectional"))
    )
    (net (code "100") (name "/4E3") (class "Default")
      (node (ref "CPLD1") (pin "19") (pinfunction "P19_19") (pintype "bidirectional"))
      (node (ref "J4") (pin "B18") (pinfunction "B18_B18") (pintype "bidirectional"))
    )
    (net (code "101") (name "/5A0") (class "Default")
      (node (ref "CPLD1") (pin "72") (pinfunction "P72_72") (pintype "bidirectional"))
      (node (ref "J5") (pin "A8") (pinfunction "A8_A8") (pintype "bidirectional"))
    )
    (net (code "102") (name "/5A1") (class "Default")
      (node (ref "CPLD1") (pin "74") (pinfunction "P74_74") (pintype "bidirectional"))
      (node (ref "J5") (pin "A9") (pinfunction "A9_A9") (pintype "bidirectional"))
    )
    (net (code "103") (name "/5A2") (class "Default")
      (node (ref "CPLD1") (pin "76") (pinfunction "P76_76") (pintype "bidirectional"))
      (node (ref "J5") (pin "A10") (pinfunction "A10_A10") (pintype "bidirectional"))
    )
    (net (code "104") (name "/5A3") (class "Default")
      (node (ref "CPLD1") (pin "77") (pinfunction "P77_77") (pintype "bidirectional"))
      (node (ref "J5") (pin "A11") (pinfunction "A11_A11") (pintype "bidirectional"))
    )
    (net (code "105") (name "/5B0") (class "Default")
      (node (ref "CPLD1") (pin "78") (pinfunction "P78_78") (pintype "bidirectional"))
      (node (ref "J5") (pin "B8") (pinfunction "B8_B8") (pintype "bidirectional"))
    )
    (net (code "106") (name "/5B1") (class "Default")
      (node (ref "CPLD1") (pin "79") (pinfunction "P79_79") (pintype "bidirectional"))
      (node (ref "J5") (pin "B9") (pinfunction "B9_B9") (pintype "bidirectional"))
    )
    (net (code "107") (name "/5B2") (class "Default")
      (node (ref "CPLD1") (pin "81") (pinfunction "P81_81") (pintype "bidirectional"))
      (node (ref "J5") (pin "B10") (pinfunction "B10_B10") (pintype "bidirectional"))
    )
    (net (code "108") (name "/5B3") (class "Default")
      (node (ref "CPLD1") (pin "89") (pinfunction "P89_89") (pintype "bidirectional"))
      (node (ref "J5") (pin "B11") (pinfunction "B11_B11") (pintype "bidirectional"))
    )
    (net (code "109") (name "/5C0") (class "Default")
      (node (ref "CPLD1") (pin "90") (pinfunction "P90_90") (pintype "bidirectional"))
      (node (ref "J5") (pin "A12") (pinfunction "A12_A12") (pintype "bidirectional"))
    )
    (net (code "110") (name "/5C1") (class "Default")
      (node (ref "CPLD1") (pin "91") (pinfunction "P91_91") (pintype "bidirectional"))
      (node (ref "J5") (pin "A13") (pinfunction "A13_A13") (pintype "bidirectional"))
    )
    (net (code "111") (name "/5C2") (class "Default")
      (node (ref "CPLD1") (pin "92") (pinfunction "P92_92") (pintype "bidirectional"))
      (node (ref "J5") (pin "B12") (pinfunction "B12_B12") (pintype "bidirectional"))
    )
    (net (code "112") (name "/5C3") (class "Default")
      (node (ref "CPLD1") (pin "94") (pinfunction "P94_94") (pintype "bidirectional"))
      (node (ref "J5") (pin "B13") (pinfunction "B13_B13") (pintype "bidirectional"))
    )
    (net (code "113") (name "/5D0") (class "Default")
      (node (ref "CPLD1") (pin "80") (pinfunction "P80/NC_80") (pintype "bidirectional"))
      (node (ref "J5") (pin "A15") (pinfunction "A15_A15") (pintype "bidirectional"))
    )
    (net (code "114") (name "/5D1") (class "Default")
      (node (ref "CPLD1") (pin "82") (pinfunction "P82/NC_82") (pintype "bidirectional"))
      (node (ref "J5") (pin "A16") (pinfunction "A16_A16") (pintype "bidirectional"))
    )
    (net (code "115") (name "/5D2") (class "Default")
      (node (ref "CPLD1") (pin "85") (pinfunction "P85/NC_85") (pintype "bidirectional"))
      (node (ref "J5") (pin "A17") (pinfunction "A17_A17") (pintype "bidirectional"))
    )
    (net (code "116") (name "/5D3") (class "Default")
      (node (ref "CPLD1") (pin "86") (pinfunction "P86/NC_86") (pintype "bidirectional"))
      (node (ref "J5") (pin "A18") (pinfunction "A18_A18") (pintype "bidirectional"))
    )
    (net (code "117") (name "/5E0") (class "Default")
      (node (ref "CPLD1") (pin "87") (pinfunction "P87/NC_87") (pintype "bidirectional"))
      (node (ref "J5") (pin "B15") (pinfunction "B15_B15") (pintype "bidirectional"))
    )
    (net (code "118") (name "/5E1") (class "Default")
      (node (ref "CPLD1") (pin "93") (pinfunction "P93/NC_93") (pintype "bidirectional"))
      (node (ref "J5") (pin "B16") (pinfunction "B16_B16") (pintype "bidirectional"))
    )
    (net (code "119") (name "/5E2") (class "Default")
      (node (ref "CPLD1") (pin "95") (pinfunction "P95/NC_95") (pintype "bidirectional"))
      (node (ref "J5") (pin "B17") (pinfunction "B17_B17") (pintype "bidirectional"))
    )
    (net (code "120") (name "/5E3") (class "Default")
      (node (ref "CPLD1") (pin "96") (pinfunction "P96/NC_96") (pintype "bidirectional"))
      (node (ref "J5") (pin "B18") (pinfunction "B18_B18") (pintype "bidirectional"))
    )
    (net (code "121") (name "/5ND") (class "Default")
      (node (ref "J5") (pin "A14") (pinfunction "A14_A14") (pintype "bidirectional"))
    )
    (net (code "122") (name "/5V") (class "Default")
      (node (ref "J0") (pin "B14") (pinfunction "B14_B14") (pintype "bidirectional"))
      (node (ref "J1") (pin "B14") (pinfunction "B14_B14") (pintype "bidirectional"))
      (node (ref "J2") (pin "B14") (pinfunction "B14_B14") (pintype "bidirectional"))
      (node (ref "J3") (pin "B14") (pinfunction "B14_B14") (pintype "bidirectional"))
      (node (ref "J4") (pin "B14") (pinfunction "B14_B14") (pintype "bidirectional"))
      (node (ref "J5") (pin "B14") (pinfunction "B14_B14") (pintype "bidirectional"))
    )
    (net (code "123") (name "/12V") (class "Default")
      (node (ref "J0") (pin "B4") (pinfunction "B4_B4") (pintype "bidirectional"))
      (node (ref "J1") (pin "B4") (pinfunction "B4_B4") (pintype "bidirectional"))
      (node (ref "J2") (pin "B4") (pinfunction "B4_B4") (pintype "bidirectional"))
      (node (ref "J3") (pin "B4") (pinfunction "B4_B4") (pintype "bidirectional"))
      (node (ref "J4") (pin "B4") (pinfunction "B4_B4") (pintype "bidirectional"))
      (node (ref "J5") (pin "B4") (pinfunction "B4_B4") (pintype "bidirectional"))
    )
    (net (code "124") (name "/CA0") (class "Default")
      (node (ref "CPLD0") (pin "52") (pinfunction "P52_52") (pintype "bidirectional"))
      (node (ref "CPLD1") (pin "52") (pinfunction "P52_52") (pintype "bidirectional"))
    )
    (net (code "125") (name "/CA1") (class "Default")
      (node (ref "CPLD0") (pin "53") (pinfunction "P53_53") (pintype "bidirectional"))
      (node (ref "CPLD1") (pin "53") (pinfunction "P53_53") (pintype "bidirectional"))
    )
    (net (code "126") (name "/CA2") (class "Default")
      (node (ref "CPLD0") (pin "55") (pinfunction "P55_55") (pintype "bidirectional"))
      (node (ref "CPLD1") (pin "55") (pinfunction "P55_55") (pintype "bidirectional"))
    )
    (net (code "127") (name "/CA3") (class "Default")
      (node (ref "CPLD0") (pin "56") (pinfunction "P56_56") (pintype "bidirectional"))
      (node (ref "CPLD1") (pin "56") (pinfunction "P56_56") (pintype "bidirectional"))
    )
    (net (code "128") (name "/CB0") (class "Default")
      (node (ref "CPLD0") (pin "58") (pinfunction "P58_58") (pintype "bidirectional"))
      (node (ref "CPLD1") (pin "58") (pinfunction "P58_58") (pintype "bidirectional"))
    )
    (net (code "129") (name "/CB1") (class "Default")
      (node (ref "CPLD0") (pin "60") (pinfunction "P60_60") (pintype "bidirectional"))
      (node (ref "CPLD1") (pin "60") (pinfunction "P60_60") (pintype "bidirectional"))
    )
    (net (code "130") (name "/CB2") (class "Default")
      (node (ref "CPLD0") (pin "61") (pinfunction "P61_61") (pintype "bidirectional"))
      (node (ref "CPLD1") (pin "61") (pinfunction "P61_61") (pintype "bidirectional"))
    )
    (net (code "131") (name "/CB3") (class "Default")
      (node (ref "CPLD0") (pin "64") (pinfunction "P64_64") (pintype "bidirectional"))
      (node (ref "CPLD1") (pin "64") (pinfunction "P64_64") (pintype "bidirectional"))
    )
    (net (code "132") (name "/CC0") (class "Default")
      (node (ref "CPLD0") (pin "67") (pinfunction "P67_67") (pintype "bidirectional"))
      (node (ref "CPLD1") (pin "67") (pinfunction "P67_67") (pintype "bidirectional"))
    )
    (net (code "133") (name "/CC1") (class "Default")
      (node (ref "CPLD0") (pin "68") (pinfunction "P68_68") (pintype "bidirectional"))
      (node (ref "CPLD1") (pin "68") (pinfunction "P68_68") (pintype "bidirectional"))
    )
    (net (code "134") (name "/CC2") (class "Default")
      (node (ref "CPLD0") (pin "70") (pinfunction "P70_70") (pintype "bidirectional"))
      (node (ref "CPLD1") (pin "70") (pinfunction "P70_70") (pintype "bidirectional"))
    )
    (net (code "135") (name "/CC3") (class "Default")
      (node (ref "CPLD0") (pin "71") (pinfunction "P71_71") (pintype "bidirectional"))
      (node (ref "CPLD1") (pin "71") (pinfunction "P71_71") (pintype "bidirectional"))
    )
    (net (code "136") (name "/CD0") (class "Default")
      (node (ref "CPLD0") (pin "44") (pinfunction "P44/NC_44") (pintype "bidirectional"))
      (node (ref "CPLD1") (pin "44") (pinfunction "P44/NC_44") (pintype "bidirectional"))
    )
    (net (code "137") (name "/CD1") (class "Default")
      (node (ref "CPLD0") (pin "46") (pinfunction "P46/NC_46") (pintype "bidirectional"))
      (node (ref "CPLD1") (pin "46") (pinfunction "P46/NC_46") (pintype "bidirectional"))
    )
    (net (code "138") (name "/CD2") (class "Default")
      (node (ref "CPLD0") (pin "54") (pinfunction "P54/NC_54") (pintype "bidirectional"))
      (node (ref "CPLD1") (pin "54") (pinfunction "P54/NC_54") (pintype "bidirectional"))
    )
    (net (code "139") (name "/CD3") (class "Default")
      (node (ref "CPLD0") (pin "59") (pinfunction "P59/NC_59") (pintype "bidirectional"))
      (node (ref "CPLD1") (pin "59") (pinfunction "P59/NC_59") (pintype "bidirectional"))
    )
    (net (code "140") (name "/CE0") (class "Default")
      (node (ref "CPLD0") (pin "63") (pinfunction "P63/NC_63") (pintype "bidirectional"))
      (node (ref "CPLD1") (pin "63") (pinfunction "P63/NC_63") (pintype "bidirectional"))
    )
    (net (code "141") (name "/CE1") (class "Default")
      (node (ref "CPLD0") (pin "65") (pinfunction "P65/NC_65") (pintype "bidirectional"))
      (node (ref "CPLD1") (pin "65") (pinfunction "P65/NC_65") (pintype "bidirectional"))
    )
    (net (code "142") (name "/CE2") (class "Default")
      (node (ref "CPLD0") (pin "66") (pinfunction "P66/NC_66") (pintype "bidirectional"))
      (node (ref "CPLD1") (pin "66") (pinfunction "P66/NC_66") (pintype "bidirectional"))
    )
    (net (code "143") (name "/CE3") (class "Default")
      (node (ref "CPLD0") (pin "73") (pinfunction "P73/NC_73") (pintype "bidirectional"))
      (node (ref "CPLD1") (pin "73") (pinfunction "P73/NC_73") (pintype "bidirectional"))
    )
    (net (code "144") (name "/GCLK") (class "Default")
      (node (ref "J0") (pin "B6") (pinfunction "B6_B6") (pintype "bidirectional"))
      (node (ref "J1") (pin "B6") (pinfunction "B6_B6") (pintype "bidirectional"))
      (node (ref "J2") (pin "B6") (pinfunction "B6_B6") (pintype "bidirectional"))
      (node (ref "J3") (pin "B6") (pinfunction "B6_B6") (pintype "bidirectional"))
      (node (ref "J4") (pin "B6") (pinfunction "B6_B6") (pintype "bidirectional"))
      (node (ref "J5") (pin "B6") (pinfunction "B6_B6") (pintype "bidirectional"))
    )
    (net (code "145") (name "/GRST") (class "Default")
      (node (ref "J0") (pin "B5") (pinfunction "B5_B5") (pintype "bidirectional"))
      (node (ref "J1") (pin "B5") (pinfunction "B5_B5") (pintype "bidirectional"))
      (node (ref "J2") (pin "B5") (pinfunction "B5_B5") (pintype "bidirectional"))
      (node (ref "J3") (pin "B5") (pinfunction "B5_B5") (pintype "bidirectional"))
      (node (ref "J4") (pin "B5") (pinfunction "B5_B5") (pintype "bidirectional"))
      (node (ref "J5") (pin "B5") (pinfunction "B5_B5") (pintype "bidirectional"))
    )
    (net (code "146") (name "/SCL") (class "Default")
      (node (ref "J0") (pin "A5") (pinfunction "A5_A5") (pintype "bidirectional"))
      (node (ref "J1") (pin "A5") (pinfunction "A5_A5") (pintype "bidirectional"))
      (node (ref "J2") (pin "A5") (pinfunction "A5_A5") (pintype "bidirectional"))
      (node (ref "J3") (pin "A5") (pinfunction "A5_A5") (pintype "bidirectional"))
      (node (ref "J4") (pin "A5") (pinfunction "A5_A5") (pintype "bidirectional"))
      (node (ref "J5") (pin "A5") (pinfunction "A5_A5") (pintype "bidirectional"))
    )
    (net (code "147") (name "/SDA") (class "Default")
      (node (ref "J0") (pin "A6") (pinfunction "A6_A6") (pintype "bidirectional"))
      (node (ref "J1") (pin "A6") (pinfunction "A6_A6") (pintype "bidirectional"))
      (node (ref "J2") (pin "A6") (pinfunction "A6_A6") (pintype "bidirectional"))
      (node (ref "J3") (pin "A6") (pinfunction "A6_A6") (pintype "bidirectional"))
      (node (ref "J4") (pin "A6") (pinfunction "A6_A6") (pintype "bidirectional"))
      (node (ref "J5") (pin "A6") (pinfunction "A6_A6") (pintype "bidirectional"))
    )
    (net (code "148") (name "/SENSE0") (class "Default")
      (node (ref "G4") (pin "6") (pinfunction "S_6") (pintype "input"))
      (node (ref "J0") (pin "B3") (pinfunction "B3_B3") (pintype "bidirectional"))
      (node (ref "L0") (pin "C") (pinfunction "C_C") (pintype "passive"))
      (node (ref "R1") (pin "1") (pinfunction "1_1") (pintype "passive"))
    )
    (net (code "149") (name "/SENSE1") (class "Default")
      (node (ref "G5") (pin "6") (pinfunction "S_6") (pintype "input"))
      (node (ref "J1") (pin "A3") (pinfunction "A3_A3") (pintype "bidirectional"))
      (node (ref "L1") (pin "C") (pinfunction "C_C") (pintype "passive"))
      (node (ref "R2") (pin "1") (pinfunction "1_1") (pintype "passive"))
    )
    (net (code "150") (name "/SENSE2") (class "Default")
      (node (ref "G6") (pin "6") (pinfunction "S_6") (pintype "input"))
      (node (ref "J2") (pin "A3") (pinfunction "A3_A3") (pintype "bidirectional"))
      (node (ref "L2") (pin "C") (pinfunction "C_C") (pintype "passive"))
      (node (ref "R3") (pin "1") (pinfunction "1_1") (pintype "passive"))
    )
    (net (code "151") (name "/SENSE3") (class "Default")
      (node (ref "G7") (pin "6") (pinfunction "S_6") (pintype "input"))
      (node (ref "J3") (pin "A3") (pinfunction "A3_A3") (pintype "bidirectional"))
      (node (ref "L3") (pin "C") (pinfunction "C_C") (pintype "passive"))
      (node (ref "R4") (pin "1") (pinfunction "1_1") (pintype "passive"))
    )
    (net (code "152") (name "/SENSE4") (class "Default")
      (node (ref "G1") (pin "6") (pinfunction "S_6") (pintype "input"))
      (node (ref "J4") (pin "A3") (pinfunction "A3_A3") (pintype "bidirectional"))
      (node (ref "L4") (pin "C") (pinfunction "C_C") (pintype "passive"))
      (node (ref "R9") (pin "1") (pinfunction "1_1") (pintype "passive"))
    )
    (net (code "153") (name "/SENSE5") (class "Default")
      (node (ref "G2") (pin "6") (pinfunction "S_6") (pintype "input"))
      (node (ref "J5") (pin "A3") (pinfunction "A3_A3") (pintype "bidirectional"))
      (node (ref "L5") (pin "C") (pinfunction "C_C") (pintype "passive"))
      (node (ref "R11") (pin "1") (pinfunction "1_1") (pintype "passive"))
    )
    (net (code "154") (name "/TCK") (class "Default")
      (node (ref "CPLD0") (pin "48") (pinfunction "TCK_48") (pintype "bidirectional"))
      (node (ref "CPLD1") (pin "48") (pinfunction "TCK_48") (pintype "bidirectional"))
      (node (ref "J0") (pin "B2") (pinfunction "B2_B2") (pintype "bidirectional"))
      (node (ref "J1") (pin "B2") (pinfunction "B2_B2") (pintype "bidirectional"))
      (node (ref "J2") (pin "B2") (pinfunction "B2_B2") (pintype "bidirectional"))
      (node (ref "J3") (pin "B2") (pinfunction "B2_B2") (pintype "bidirectional"))
      (node (ref "J4") (pin "B2") (pinfunction "B2_B2") (pintype "bidirectional"))
      (node (ref "J5") (pin "B2") (pinfunction "B2_B2") (pintype "bidirectional"))
    )
    (net (code "155") (name "/TDI0{slash}TDOC0") (class "Default")
      (node (ref "CPLD0") (pin "83") (pinfunction "TDO_83") (pintype "bidirectional"))
      (node (ref "G4") (pin "1") (pinfunction "I1_1") (pintype "input"))
      (node (ref "J0") (pin "B1") (pinfunction "B1_B1") (pintype "bidirectional"))
    )
    (net (code "156") (name "/TDI1") (class "Default")
      (node (ref "G4") (pin "4") (pinfunction "Y_4") (pintype "output"))
      (node (ref "G5") (pin "1") (pinfunction "I1_1") (pintype "input"))
      (node (ref "J1") (pin "B1") (pinfunction "B1_B1") (pintype "bidirectional"))
    )
    (net (code "157") (name "/TDI2") (class "Default")
      (node (ref "G5") (pin "4") (pinfunction "Y_4") (pintype "output"))
      (node (ref "G6") (pin "1") (pinfunction "I1_1") (pintype "input"))
      (node (ref "J2") (pin "B1") (pinfunction "B1_B1") (pintype "bidirectional"))
    )
    (net (code "158") (name "/TDI3") (class "Default")
      (node (ref "G6") (pin "4") (pinfunction "Y_4") (pintype "output"))
      (node (ref "G7") (pin "1") (pinfunction "I1_1") (pintype "input"))
      (node (ref "J3") (pin "B1") (pinfunction "B1_B1") (pintype "bidirectional"))
    )
    (net (code "159") (name "/TDI4") (class "Default")
      (node (ref "G1") (pin "1") (pinfunction "I1_1") (pintype "input"))
      (node (ref "G7") (pin "4") (pinfunction "Y_4") (pintype "output"))
      (node (ref "J4") (pin "B1") (pinfunction "B1_B1") (pintype "bidirectional"))
    )
    (net (code "160") (name "/TDI5") (class "Default")
      (node (ref "G1") (pin "4") (pinfunction "Y_4") (pintype "output"))
      (node (ref "G2") (pin "1") (pinfunction "I1_1") (pintype "input"))
      (node (ref "J5") (pin "B1") (pinfunction "B1_B1") (pintype "bidirectional"))
    )
    (net (code "161") (name "/TDIC0{slash}TDOC1") (class "Default")
      (node (ref "CPLD0") (pin "45") (pinfunction "TDI_45") (pintype "bidirectional"))
      (node (ref "CPLD1") (pin "83") (pinfunction "TDO_83") (pintype "bidirectional"))
    )
    (net (code "162") (name "/TDIC1") (class "Default")
      (node (ref "CPLD1") (pin "45") (pinfunction "TDI_45") (pintype "bidirectional"))
      (node (ref "G2") (pin "4") (pinfunction "Y_4") (pintype "output"))
    )
    (net (code "163") (name "/TDO0") (class "Default")
      (node (ref "G4") (pin "3") (pinfunction "I0_3") (pintype "input"))
      (node (ref "J0") (pin "A1") (pinfunction "A1_A1") (pintype "bidirectional"))
    )
    (net (code "164") (name "/TDO1") (class "Default")
      (node (ref "G5") (pin "3") (pinfunction "I0_3") (pintype "input"))
      (node (ref "J1") (pin "A1") (pinfunction "A1_A1") (pintype "bidirectional"))
    )
    (net (code "165") (name "/TDO2") (class "Default")
      (node (ref "G6") (pin "3") (pinfunction "I0_3") (pintype "input"))
      (node (ref "J2") (pin "A1") (pinfunction "A1_A1") (pintype "bidirectional"))
    )
    (net (code "166") (name "/TDO3") (class "Default")
      (node (ref "G7") (pin "3") (pinfunction "I0_3") (pintype "input"))
      (node (ref "J3") (pin "A1") (pinfunction "A1_A1") (pintype "bidirectional"))
    )
    (net (code "167") (name "/TDO4") (class "Default")
      (node (ref "G1") (pin "3") (pinfunction "I0_3") (pintype "input"))
      (node (ref "J4") (pin "A1") (pinfunction "A1_A1") (pintype "bidirectional"))
    )
    (net (code "168") (name "/TDO5") (class "Default")
      (node (ref "G2") (pin "3") (pinfunction "I0_3") (pintype "input"))
      (node (ref "J5") (pin "A1") (pinfunction "A1_A1") (pintype "bidirectional"))
    )
    (net (code "169") (name "/TMS") (class "Default")
      (node (ref "CPLD0") (pin "47") (pinfunction "TMS_47") (pintype "bidirectional"))
      (node (ref "CPLD1") (pin "47") (pinfunction "TMS_47") (pintype "bidirectional"))
      (node (ref "J0") (pin "A2") (pinfunction "A2_A2") (pintype "bidirectional"))
      (node (ref "J1") (pin "A2") (pinfunction "A2_A2") (pintype "bidirectional"))
      (node (ref "J2") (pin "A2") (pinfunction "A2_A2") (pintype "bidirectional"))
      (node (ref "J3") (pin "A2") (pinfunction "A2_A2") (pintype "bidirectional"))
      (node (ref "J4") (pin "A2") (pinfunction "A2_A2") (pintype "bidirectional"))
      (node (ref "J5") (pin "A2") (pinfunction "A2_A2") (pintype "bidirectional"))
    )
    (net (code "170") (name "1.8V") (class "Default")
      (node (ref "C2") (pin "1") (pinfunction "1_1") (pintype "passive"))
      (node (ref "C5") (pin "1") (pinfunction "1_1") (pintype "passive"))
      (node (ref "C7") (pin "1") (pinfunction "1_1") (pintype "passive"))
      (node (ref "C8") (pin "1") (pinfunction "1_1") (pintype "passive"))
      (node (ref "CPLD0") (pin "26") (pinfunction "VCC_26") (pintype "bidirectional"))
      (node (ref "CPLD0") (pin "57") (pinfunction "VCC_57") (pintype "bidirectional"))
      (node (ref "CPLD1") (pin "26") (pinfunction "VCC_26") (pintype "bidirectional"))
      (node (ref "CPLD1") (pin "57") (pinfunction "VCC_57") (pintype "bidirectional"))
      (node (ref "J0") (pin "B7") (pinfunction "B7_B7") (pintype "bidirectional"))
      (node (ref "J1") (pin "B7") (pinfunction "B7_B7") (pintype "bidirectional"))
      (node (ref "J2") (pin "B7") (pinfunction "B7_B7") (pintype "bidirectional"))
      (node (ref "J3") (pin "B7") (pinfunction "B7_B7") (pintype "bidirectional"))
      (node (ref "J4") (pin "B7") (pinfunction "B7_B7") (pintype "bidirectional"))
      (node (ref "J5") (pin "B7") (pinfunction "B7_B7") (pintype "bidirectional"))
    )
    (net (code "171") (name "3.3V") (class "Default")
      (node (ref "C1") (pin "1") (pinfunction "1_1") (pintype "passive"))
      (node (ref "C3") (pin "1") (pinfunction "1_1") (pintype "passive"))
      (node (ref "C4") (pin "1") (pinfunction "1_1") (pintype "passive"))
      (node (ref "C6") (pin "1") (pinfunction "1_1") (pintype "passive"))
      (node (ref "CPLD0") (pin "20") (pinfunction "VCCIO1_20") (pintype "bidirectional"))
      (node (ref "CPLD0") (pin "38") (pinfunction "VCCIO1_38") (pintype "bidirectional"))
      (node (ref "CPLD0") (pin "5") (pinfunction "VAUX_5") (pintype "bidirectional"))
      (node (ref "CPLD0") (pin "51") (pinfunction "VCCIO1_51") (pintype "bidirectional"))
      (node (ref "CPLD0") (pin "88") (pinfunction "VCCIO2_88") (pintype "bidirectional"))
      (node (ref "CPLD0") (pin "98") (pinfunction "VCCIO2_98") (pintype "bidirectional"))
      (node (ref "CPLD1") (pin "20") (pinfunction "VCCIO1_20") (pintype "bidirectional"))
      (node (ref "CPLD1") (pin "38") (pinfunction "VCCIO1_38") (pintype "bidirectional"))
      (node (ref "CPLD1") (pin "5") (pinfunction "VAUX_5") (pintype "bidirectional"))
      (node (ref "CPLD1") (pin "51") (pinfunction "VCCIO1_51") (pintype "bidirectional"))
      (node (ref "CPLD1") (pin "88") (pinfunction "VCCIO2_88") (pintype "bidirectional"))
      (node (ref "CPLD1") (pin "98") (pinfunction "VCCIO2_98") (pintype "bidirectional"))
      (node (ref "G1") (pin "5") (pinfunction "VCC_5") (pintype "power_in"))
      (node (ref "G2") (pin "5") (pinfunction "VCC_5") (pintype "power_in"))
      (node (ref "G4") (pin "5") (pinfunction "VCC_5") (pintype "power_in"))
      (node (ref "G5") (pin "5") (pinfunction "VCC_5") (pintype "power_in"))
      (node (ref "G6") (pin "5") (pinfunction "VCC_5") (pintype "power_in"))
      (node (ref "G7") (pin "5") (pinfunction "VCC_5") (pintype "power_in"))
      (node (ref "J0") (pin "A7") (pinfunction "A7_A7") (pintype "bidirectional"))
      (node (ref "J1") (pin "A7") (pinfunction "A7_A7") (pintype "bidirectional"))
      (node (ref "J2") (pin "A7") (pinfunction "A7_A7") (pintype "bidirectional"))
      (node (ref "J3") (pin "A7") (pinfunction "A7_A7") (pintype "bidirectional"))
      (node (ref "J4") (pin "A7") (pinfunction "A7_A7") (pintype "bidirectional"))
      (node (ref "J5") (pin "A7") (pinfunction "A7_A7") (pintype "bidirectional"))
      (node (ref "R1") (pin "2") (pinfunction "2_2") (pintype "passive"))
      (node (ref "R10") (pin "1") (pinfunction "1_1") (pintype "passive"))
      (node (ref "R11") (pin "2") (pinfunction "2_2") (pintype "passive"))
      (node (ref "R12") (pin "1") (pinfunction "1_1") (pintype "passive"))
      (node (ref "R2") (pin "2") (pinfunction "2_2") (pintype "passive"))
      (node (ref "R3") (pin "2") (pinfunction "2_2") (pintype "passive"))
      (node (ref "R4") (pin "2") (pinfunction "2_2") (pintype "passive"))
      (node (ref "R5") (pin "1") (pinfunction "1_1") (pintype "passive"))
      (node (ref "R6") (pin "1") (pinfunction "1_1") (pintype "passive"))
      (node (ref "R7") (pin "1") (pinfunction "1_1") (pintype "passive"))
      (node (ref "R8") (pin "1") (pinfunction "1_1") (pintype "passive"))
      (node (ref "R9") (pin "2") (pinfunction "2_2") (pintype "passive"))
    )
    (net (code "172") (name "GND") (class "Default")
      (node (ref "C1") (pin "2") (pinfunction "2_2") (pintype "passive"))
      (node (ref "C2") (pin "2") (pinfunction "2_2") (pintype "passive"))
      (node (ref "C3") (pin "2") (pinfunction "2_2") (pintype "passive"))
      (node (ref "C4") (pin "2") (pinfunction "2_2") (pintype "passive"))
      (node (ref "C5") (pin "2") (pinfunction "2_2") (pintype "passive"))
      (node (ref "C6") (pin "2") (pinfunction "2_2") (pintype "passive"))
      (node (ref "C7") (pin "2") (pinfunction "2_2") (pintype "passive"))
      (node (ref "C8") (pin "2") (pinfunction "2_2") (pintype "passive"))
      (node (ref "CPLD0") (pin "100") (pinfunction "GND_100") (pintype "bidirectional"))
      (node (ref "CPLD0") (pin "21") (pinfunction "GND_21") (pintype "bidirectional"))
      (node (ref "CPLD0") (pin "25") (pinfunction "GND_25") (pintype "bidirectional"))
      (node (ref "CPLD0") (pin "31") (pinfunction "GND_31") (pintype "bidirectional"))
      (node (ref "CPLD0") (pin "62") (pinfunction "GND_62") (pintype "bidirectional"))
      (node (ref "CPLD0") (pin "69") (pinfunction "GND_69") (pintype "bidirectional"))
      (node (ref "CPLD0") (pin "75") (pinfunction "GND_75") (pintype "bidirectional"))
      (node (ref "CPLD0") (pin "84") (pinfunction "GND_84") (pintype "bidirectional"))
      (node (ref "CPLD1") (pin "100") (pinfunction "GND_100") (pintype "bidirectional"))
      (node (ref "CPLD1") (pin "21") (pinfunction "GND_21") (pintype "bidirectional"))
      (node (ref "CPLD1") (pin "25") (pinfunction "GND_25") (pintype "bidirectional"))
      (node (ref "CPLD1") (pin "31") (pinfunction "GND_31") (pintype "bidirectional"))
      (node (ref "CPLD1") (pin "62") (pinfunction "GND_62") (pintype "bidirectional"))
      (node (ref "CPLD1") (pin "69") (pinfunction "GND_69") (pintype "bidirectional"))
      (node (ref "CPLD1") (pin "75") (pinfunction "GND_75") (pintype "bidirectional"))
      (node (ref "CPLD1") (pin "84") (pinfunction "GND_84") (pintype "bidirectional"))
      (node (ref "G1") (pin "2") (pinfunction "GND_2") (pintype "power_in"))
      (node (ref "G2") (pin "2") (pinfunction "GND_2") (pintype "power_in"))
      (node (ref "G4") (pin "2") (pinfunction "GND_2") (pintype "power_in"))
      (node (ref "G5") (pin "2") (pinfunction "GND_2") (pintype "power_in"))
      (node (ref "G6") (pin "2") (pinfunction "GND_2") (pintype "power_in"))
      (node (ref "G7") (pin "2") (pinfunction "GND_2") (pintype "power_in"))
      (node (ref "J0") (pin "A14") (pinfunction "A14_A14") (pintype "bidirectional"))
      (node (ref "J0") (pin "A3") (pinfunction "A3_A3") (pintype "bidirectional"))
      (node (ref "J0") (pin "A4") (pinfunction "A4_A4") (pintype "bidirectional"))
      (node (ref "J1") (pin "A14") (pinfunction "A14_A14") (pintype "bidirectional"))
      (node (ref "J1") (pin "A4") (pinfunction "A4_A4") (pintype "bidirectional"))
      (node (ref "J1") (pin "B3") (pinfunction "B3_B3") (pintype "bidirectional"))
      (node (ref "J2") (pin "A14") (pinfunction "A14_A14") (pintype "bidirectional"))
      (node (ref "J2") (pin "A4") (pinfunction "A4_A4") (pintype "bidirectional"))
      (node (ref "J2") (pin "B3") (pinfunction "B3_B3") (pintype "bidirectional"))
      (node (ref "J3") (pin "A14") (pinfunction "A14_A14") (pintype "bidirectional"))
      (node (ref "J3") (pin "A4") (pinfunction "A4_A4") (pintype "bidirectional"))
      (node (ref "J3") (pin "B3") (pinfunction "B3_B3") (pintype "bidirectional"))
      (node (ref "J4") (pin "A14") (pinfunction "A14_A14") (pintype "bidirectional"))
      (node (ref "J4") (pin "A4") (pinfunction "A4_A4") (pintype "bidirectional"))
      (node (ref "J4") (pin "B3") (pinfunction "B3_B3") (pintype "bidirectional"))
      (node (ref "J5") (pin "A4") (pinfunction "A4_A4") (pintype "bidirectional"))
      (node (ref "J5") (pin "B3") (pinfunction "B3_B3") (pintype "bidirectional"))
    )
    (net (code "173") (name "Net-(L0-PadA)") (class "Default")
      (node (ref "L0") (pin "A") (pinfunction "A_A") (pintype "passive"))
      (node (ref "R5") (pin "2") (pinfunction "2_2") (pintype "passive"))
    )
    (net (code "174") (name "Net-(L1-PadA)") (class "Default")
      (node (ref "L1") (pin "A") (pinfunction "A_A") (pintype "passive"))
      (node (ref "R6") (pin "2") (pinfunction "2_2") (pintype "passive"))
    )
    (net (code "175") (name "Net-(L2-PadA)") (class "Default")
      (node (ref "L2") (pin "A") (pinfunction "A_A") (pintype "passive"))
      (node (ref "R7") (pin "2") (pinfunction "2_2") (pintype "passive"))
    )
    (net (code "176") (name "Net-(L3-PadA)") (class "Default")
      (node (ref "L3") (pin "A") (pinfunction "A_A") (pintype "passive"))
      (node (ref "R8") (pin "2") (pinfunction "2_2") (pintype "passive"))
    )
    (net (code "177") (name "Net-(L4-PadA)") (class "Default")
      (node (ref "L4") (pin "A") (pinfunction "A_A") (pintype "passive"))
      (node (ref "R10") (pin "2") (pinfunction "2_2") (pintype "passive"))
    )
    (net (code "178") (name "Net-(L5-PadA)") (class "Default")
      (node (ref "L5") (pin "A") (pinfunction "A_A") (pintype "passive"))
      (node (ref "R12") (pin "2") (pinfunction "2_2") (pintype "passive"))
    )
  )
)
